# esquematico.net
KiCad netlist of a schematic drawn in EAGLE
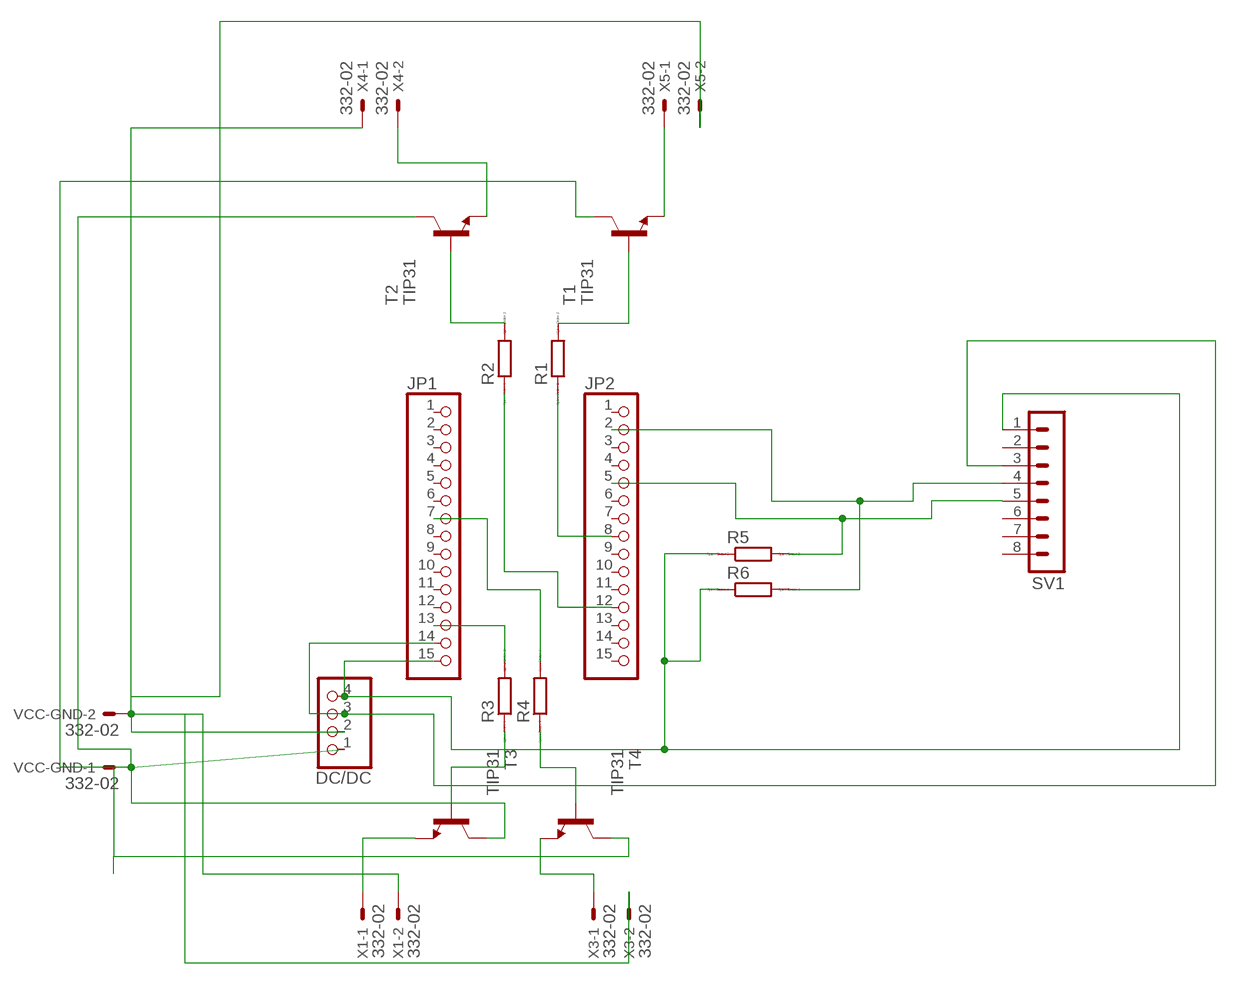
[diagram p0: schematic, sheet 1]

(export (version "E")
  (design (tool "Eeschema 10.0.6"))
  (components
    (comp (ref "DC/DC")
      (value "PINHD-1X4")
      (footprint "eagle-import:1X04")
      (libsource (lib "eagle-import") (part "PINHD-1X4"))
    )
    (comp (ref "JP1")
      (value "PINHD-1X15")
      (footprint "eagle-import:1X15")
      (libsource (lib "eagle-import") (part "PINHD-1X15"))
    )
    (comp (ref "JP2")
      (value "PINHD-1X15")
      (footprint "eagle-import:1X15")
      (libsource (lib "eagle-import") (part "PINHD-1X15"))
    )
    (comp (ref "R1")
      (value "R0207/10")
      (footprint "eagle-import:0207_10")
      (libsource (lib "eagle-import") (part "R0207/10"))
    )
    (comp (ref "R2")
      (value "R0207/10")
      (footprint "eagle-import:0207_10")
      (libsource (lib "eagle-import") (part "R0207/10"))
    )
    (comp (ref "R3")
      (value "R0207/10")
      (footprint "eagle-import:0207_10")
      (libsource (lib "eagle-import") (part "R0207/10"))
    )
    (comp (ref "R4")
      (value "R0207/10")
      (footprint "eagle-import:0207_10")
      (libsource (lib "eagle-import") (part "R0207/10"))
    )
    (comp (ref "R5")
      (value "R0207/10")
      (footprint "eagle-import:0207_10")
      (libsource (lib "eagle-import") (part "R0207/10"))
    )
    (comp (ref "R6")
      (value "R0207/10")
      (footprint "eagle-import:0207_10")
      (libsource (lib "eagle-import") (part "R0207/10"))
    )
    (comp (ref "SV1")
      (value "MA08-1")
      (footprint "eagle-import:MA08-1")
      (libsource (lib "eagle-import") (part "MA08-1"))
    )
    (comp (ref "T1")
      (value "TIP31")
      (footprint "eagle-import:TO220")
      (libsource (lib "eagle-import") (part "TIP31"))
    )
    (comp (ref "T2")
      (value "TIP31")
      (footprint "eagle-import:TO220")
      (libsource (lib "eagle-import") (part "TIP31"))
    )
    (comp (ref "T3")
      (value "TIP31")
      (footprint "eagle-import:TO220")
      (libsource (lib "eagle-import") (part "TIP31"))
    )
    (comp (ref "T4")
      (value "TIP31")
      (footprint "eagle-import:TO220")
      (libsource (lib "eagle-import") (part "TIP31"))
    )
    (comp (ref "VCC-GND")
      (value "332-02")
      (footprint "eagle-import:332-02")
      (libsource (lib "eagle-import") (part "332-02"))
    )
    (comp (ref "X1")
      (value "332-02")
      (footprint "eagle-import:332-02")
      (libsource (lib "eagle-import") (part "332-02"))
    )
    (comp (ref "X3")
      (value "332-02")
      (footprint "eagle-import:332-02")
      (libsource (lib "eagle-import") (part "332-02"))
    )
    (comp (ref "X4")
      (value "332-02")
      (footprint "eagle-import:332-02")
      (libsource (lib "eagle-import") (part "332-02"))
    )
    (comp (ref "X5")
      (value "332-02")
      (footprint "eagle-import:332-02")
      (libsource (lib "eagle-import") (part "332-02"))
    )
  )
  (nets
    (net (code "1") (name "Net-(DC/DC-Pad3)") (class "Default")
      (node (ref "DC/DC") (pin "3") (pinfunction "3_3") (pintype "passive"))
      (node (ref "JP1") (pin "14") (pinfunction "14_14") (pintype "passive"))
      (node (ref "SV1") (pin "3") (pinfunction "3_3") (pintype "passive"))
    )
    (net (code "2") (name "Net-(DC/DC-Pad4)") (class "Default")
      (node (ref "DC/DC") (pin "4") (pinfunction "4_4") (pintype "passive"))
      (node (ref "JP1") (pin "15") (pinfunction "15_15") (pintype "passive"))
      (node (ref "R5") (pin "1") (pinfunction "1_1") (pintype "passive"))
      (node (ref "R6") (pin "1") (pinfunction "1_1") (pintype "passive"))
      (node (ref "SV1") (pin "1") (pinfunction "1_1") (pintype "passive"))
    )
    (net (code "3") (name "Net-(JP1-Pad7)") (class "Default")
      (node (ref "JP1") (pin "7") (pinfunction "7_7") (pintype "passive"))
      (node (ref "R4") (pin "2") (pinfunction "2_2") (pintype "passive"))
    )
    (net (code "4") (name "Net-(JP1-Pad13)") (class "Default")
      (node (ref "JP1") (pin "13") (pinfunction "13_13") (pintype "passive"))
      (node (ref "R3") (pin "2") (pinfunction "2_2") (pintype "passive"))
    )
    (net (code "5") (name "Net-(JP2-Pad2)") (class "Default")
      (node (ref "JP2") (pin "2") (pinfunction "2_2") (pintype "passive"))
      (node (ref "R6") (pin "2") (pinfunction "2_2") (pintype "passive"))
      (node (ref "SV1") (pin "4") (pinfunction "4_4") (pintype "passive"))
    )
    (net (code "6") (name "Net-(JP2-Pad5)") (class "Default")
      (node (ref "JP2") (pin "5") (pinfunction "5_5") (pintype "passive"))
      (node (ref "R5") (pin "2") (pinfunction "2_2") (pintype "passive"))
      (node (ref "SV1") (pin "5") (pinfunction "5_5") (pintype "passive"))
    )
    (net (code "7") (name "Net-(JP2-Pad8)") (class "Default")
      (node (ref "JP2") (pin "8") (pinfunction "8_8") (pintype "passive"))
      (node (ref "R1") (pin "1") (pinfunction "1_1") (pintype "passive"))
    )
    (net (code "8") (name "Net-(JP2-Pad12)") (class "Default")
      (node (ref "JP2") (pin "12") (pinfunction "12_12") (pintype "passive"))
      (node (ref "R2") (pin "1") (pinfunction "1_1") (pintype "passive"))
    )
    (net (code "9") (name "Net-(T1-B)") (class "Default")
      (node (ref "R1") (pin "2") (pinfunction "2_2") (pintype "passive"))
      (node (ref "T1") (pin "1") (pinfunction "B_1") (pintype "passive"))
    )
    (net (code "10") (name "Net-(T1-C)") (class "Default")
      (node (ref "DC/DC") (pin "1") (pinfunction "1_1") (pintype "passive"))
      (node (ref "T1") (pin "2") (pinfunction "C_2") (pintype "passive"))
      (node (ref "T2") (pin "2") (pinfunction "C_2") (pintype "passive"))
      (node (ref "T3") (pin "2") (pinfunction "C_2") (pintype "passive"))
      (node (ref "T4") (pin "2") (pinfunction "C_2") (pintype "passive"))
      (node (ref "VCC-GND") (pin "1") (pinfunction "S_1") (pintype "passive"))
    )
    (net (code "11") (name "Net-(T1-E)") (class "Default")
      (node (ref "T1") (pin "3") (pinfunction "E_3") (pintype "passive"))
      (node (ref "X5") (pin "1") (pinfunction "S_1") (pintype "passive"))
    )
    (net (code "12") (name "Net-(T2-B)") (class "Default")
      (node (ref "R2") (pin "2") (pinfunction "2_2") (pintype "passive"))
      (node (ref "T2") (pin "1") (pinfunction "B_1") (pintype "passive"))
    )
    (net (code "13") (name "Net-(T2-E)") (class "Default")
      (node (ref "T2") (pin "3") (pinfunction "E_3") (pintype "passive"))
      (node (ref "X4") (pin "2") (pinfunction "S_2") (pintype "passive"))
    )
    (net (code "14") (name "Net-(T3-B)") (class "Default")
      (node (ref "R3") (pin "1") (pinfunction "1_1") (pintype "passive"))
      (node (ref "T3") (pin "1") (pinfunction "B_1") (pintype "passive"))
    )
    (net (code "15") (name "Net-(T3-E)") (class "Default")
      (node (ref "T3") (pin "3") (pinfunction "E_3") (pintype "passive"))
      (node (ref "X1") (pin "1") (pinfunction "S_1") (pintype "passive"))
    )
    (net (code "16") (name "Net-(T4-B)") (class "Default")
      (node (ref "R4") (pin "1") (pinfunction "1_1") (pintype "passive"))
      (node (ref "T4") (pin "1") (pinfunction "B_1") (pintype "passive"))
    )
    (net (code "17") (name "Net-(T4-E)") (class "Default")
      (node (ref "T4") (pin "3") (pinfunction "E_3") (pintype "passive"))
      (node (ref "X3") (pin "1") (pinfunction "S_1") (pintype "passive"))
    )
    (net (code "18") (name "Net-(VCC-GNDB-S)") (class "Default")
      (node (ref "DC/DC") (pin "2") (pinfunction "2_2") (pintype "passive"))
      (node (ref "VCC-GND") (pin "2") (pinfunction "S_2") (pintype "passive"))
      (node (ref "X1") (pin "2") (pinfunction "S_2") (pintype "passive"))
      (node (ref "X3") (pin "2") (pinfunction "S_2") (pintype "passive"))
      (node (ref "X4") (pin "1") (pinfunction "S_1") (pintype "passive"))
      (node (ref "X5") (pin "2") (pinfunction "S_2") (pintype "passive"))
    )
    (net (code "19") (name "unconnected-(JP1-Pad1)") (class "Default")
      (node (ref "JP1") (pin "1") (pinfunction "1_1") (pintype "passive"))
    )
    (net (code "20") (name "unconnected-(JP1-Pad2)") (class "Default")
      (node (ref "JP1") (pin "2") (pinfunction "2_2") (pintype "passive"))
    )
    (net (code "21") (name "unconnected-(JP1-Pad3)") (class "Default")
      (node (ref "JP1") (pin "3") (pinfunction "3_3") (pintype "passive"))
    )
    (net (code "22") (name "unconnected-(JP1-Pad4)") (class "Default")
      (node (ref "JP1") (pin "4") (pinfunction "4_4") (pintype "passive"))
    )
    (net (code "23") (name "unconnected-(JP1-Pad5)") (class "Default")
      (node (ref "JP1") (pin "5") (pinfunction "5_5") (pintype "passive"))
    )
    (net (code "24") (name "unconnected-(JP1-Pad6)") (class "Default")
      (node (ref "JP1") (pin "6") (pinfunction "6_6") (pintype "passive"))
    )
    (net (code "25") (name "unconnected-(JP1-Pad8)") (class "Default")
      (node (ref "JP1") (pin "8") (pinfunction "8_8") (pintype "passive"))
    )
    (net (code "26") (name "unconnected-(JP1-Pad9)") (class "Default")
      (node (ref "JP1") (pin "9") (pinfunction "9_9") (pintype "passive"))
    )
    (net (code "27") (name "unconnected-(JP1-Pad10)") (class "Default")
      (node (ref "JP1") (pin "10") (pinfunction "10_10") (pintype "passive"))
    )
    (net (code "28") (name "unconnected-(JP1-Pad11)") (class "Default")
      (node (ref "JP1") (pin "11") (pinfunction "11_11") (pintype "passive"))
    )
    (net (code "29") (name "unconnected-(JP1-Pad12)") (class "Default")
      (node (ref "JP1") (pin "12") (pinfunction "12_12") (pintype "passive"))
    )
    (net (code "30") (name "unconnected-(JP2-Pad1)") (class "Default")
      (node (ref "JP2") (pin "1") (pinfunction "1_1") (pintype "passive"))
    )
    (net (code "31") (name "unconnected-(JP2-Pad3)") (class "Default")
      (node (ref "JP2") (pin "3") (pinfunction "3_3") (pintype "passive"))
    )
    (net (code "32") (name "unconnected-(JP2-Pad4)") (class "Default")
      (node (ref "JP2") (pin "4") (pinfunction "4_4") (pintype "passive"))
    )
    (net (code "33") (name "unconnected-(JP2-Pad6)") (class "Default")
      (node (ref "JP2") (pin "6") (pinfunction "6_6") (pintype "passive"))
    )
    (net (code "34") (name "unconnected-(JP2-Pad7)") (class "Default")
      (node (ref "JP2") (pin "7") (pinfunction "7_7") (pintype "passive"))
    )
    (net (code "35") (name "unconnected-(JP2-Pad9)") (class "Default")
      (node (ref "JP2") (pin "9") (pinfunction "9_9") (pintype "passive"))
    )
    (net (code "36") (name "unconnected-(JP2-Pad10)") (class "Default")
      (node (ref "JP2") (pin "10") (pinfunction "10_10") (pintype "passive"))
    )
    (net (code "37") (name "unconnected-(JP2-Pad11)") (class "Default")
      (node (ref "JP2") (pin "11") (pinfunction "11_11") (pintype "passive"))
    )
    (net (code "38") (name "unconnected-(JP2-Pad13)") (class "Default")
      (node (ref "JP2") (pin "13") (pinfunction "13_13") (pintype "passive"))
    )
    (net (code "39") (name "unconnected-(JP2-Pad14)") (class "Default")
      (node (ref "JP2") (pin "14") (pinfunction "14_14") (pintype "passive"))
    )
    (net (code "40") (name "unconnected-(JP2-Pad15)") (class "Default")
      (node (ref "JP2") (pin "15") (pinfunction "15_15") (pintype "passive"))
    )
    (net (code "41") (name "unconnected-(SV1-Pad2)") (class "Default")
      (node (ref "SV1") (pin "2") (pinfunction "2_2") (pintype "passive"))
    )
    (net (code "42") (name "unconnected-(SV1-Pad6)") (class "Default")
      (node (ref "SV1") (pin "6") (pinfunction "6_6") (pintype "passive"))
    )
    (net (code "43") (name "unconnected-(SV1-Pad7)") (class "Default")
      (node (ref "SV1") (pin "7") (pinfunction "7_7") (pintype "passive"))
    )
    (net (code "44") (name "unconnected-(SV1-Pad8)") (class "Default")
      (node (ref "SV1") (pin "8") (pinfunction "8_8") (pintype "passive"))
    )
  )
)
